# 6_Magnetorquer_Drivers.net
KiCad netlist of a schematic drawn in Altium Designer
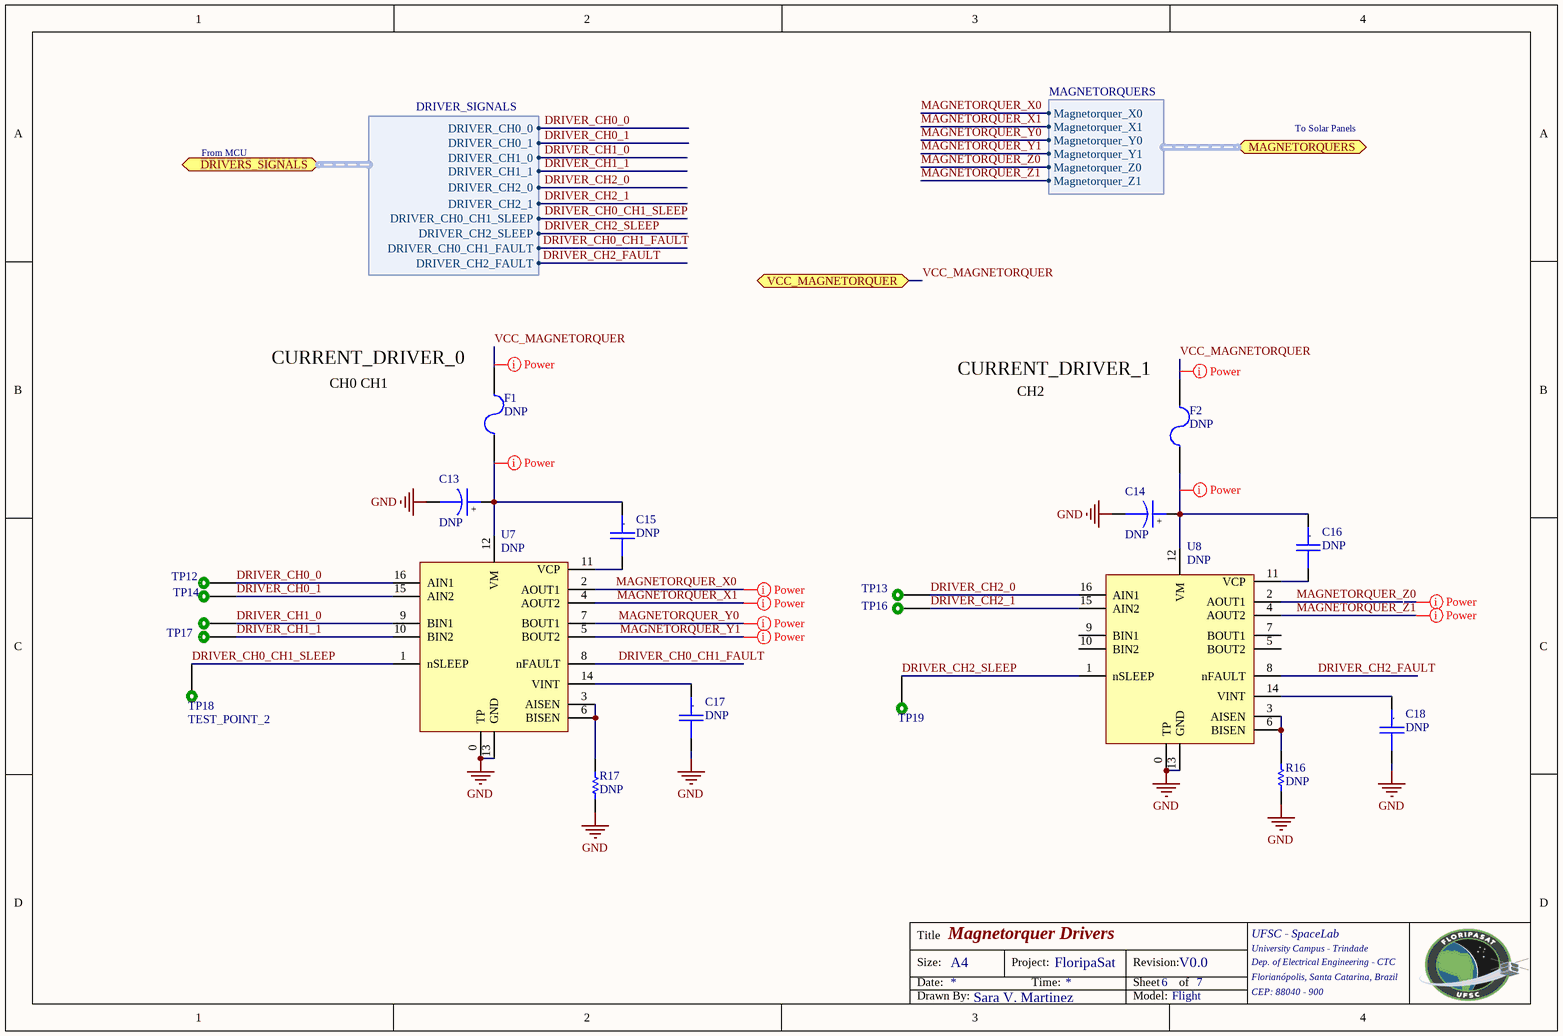
[diagram p0: 6_Magnetorquer_Drivers.SchDoc]

(export (version "E")
  (design (tool "Eeschema 10.0.6"))
  (components
    (comp (ref "C13")
      (value "DNP")
      (footprint "FloripaSatPcbLib:CC0805_Tantalum")
      (description "CAP Tantalum 10uF 10V 20% 0805")
      (fields (field (name "PARTNUMBER") "TPSP106M010R2000"))
      (libsource (lib "FloripaSatSchlib") (part "Cap_Tant_SMD_10uF_10V_0805"))
    )
    (comp (ref "C14")
      (value "DNP")
      (footprint "FloripaSatPcbLib:CC0805_Tantalum")
      (description "CAP Tantalum 10uF 10V 20% 0805")
      (fields (field (name "PARTNUMBER") "TPSP106M010R2000"))
      (libsource (lib "FloripaSatSchlib") (part "Cap_Tant_SMD_10uF_10V_0805"))
    )
    (comp (ref "C15")
      (value "DNP")
      (footprint "CC0805")
      (description "CAP CER 0.01uF 50V 10% X7R 0805")
      (fields (field (name "PARTNUMBER") "CL21B103KAANNNC"))
      (libsource (lib "FloripaSatSchlib") (part "Cap_Cer_X7R_0.01uF_50V_0805"))
    )
    (comp (ref "C16")
      (value "DNP")
      (footprint "CC0805")
      (description "CAP CER 0.01uF 50V 10% X7R 0805")
      (fields (field (name "PARTNUMBER") "CL21B103KAANNNC"))
      (libsource (lib "FloripaSatSchlib") (part "Cap_Cer_X7R_0.01uF_50V_0805"))
    )
    (comp (ref "C17")
      (value "DNP")
      (footprint "CC0805")
      (description "CAP CER 2.2uF 16V 0805")
      (fields (field (name "PARTNUMBER") "C2012X7R1C225K125AB"))
      (libsource (lib "FloripaSatSchlib") (part "Cap_Cer_X7R_2.2uF_16V_0805"))
    )
    (comp (ref "C18")
      (value "DNP")
      (footprint "CC0805")
      (description "CAP CER 2.2uF 16V 0805")
      (fields (field (name "PARTNUMBER") "C2012X7R1C225K125AB"))
      (libsource (lib "FloripaSatSchlib") (part "Cap_Cer_X7R_2.2uF_16V_0805"))
    )
    (comp (ref "F1")
      (value "DNP")
      (footprint "1206")
      (description "Surface Mount Fuses SMD FA 4A")
      (fields (field (name "PARTNUMBER") "0437.375WR") (field (name "PUBLISHER") "Altium Limited"))
      (libsource (lib "FloripaSatSchlib") (part "Fuse"))
    )
    (comp (ref "F2")
      (value "DNP")
      (footprint "1206")
      (description "Surface Mount Fuses SMD FA 4A")
      (fields (field (name "PARTNUMBER") "0437.375WR") (field (name "PUBLISHER") "Altium Limited"))
      (libsource (lib "FloripaSatSchlib") (part "Fuse"))
    )
    (comp (ref "R16")
      (value "DNP")
      (footprint "FloripaSatPcbLib:0805")
      (description "RES 0.2 OHM -0.2W 1% 0805")
      (fields (field (name "PARTNUMBER") "RL1220S-R20-F"))
      (libsource (lib "FloripaSatSchlib") (part "R0.015R_1%_0.5W_0805"))
    )
    (comp (ref "R17")
      (value "DNP")
      (footprint "FloripaSatPcbLib:0805")
      (description "RES 0.2 OHM - 0.2W 1% 0805")
      (fields (field (name "PARTNUMBER") "RL1220S-R20-F"))
      (libsource (lib "FloripaSatSchlib") (part "R0.015R_1%_0.5W_0805"))
    )
    (comp (ref "TP12")
      (value "TEST_POINT_2")
      (footprint "TEST_POINT_2")
      (description "Test point")
      (libsource (lib "FloripaSatSchlib") (part "TEST_POINT_2"))
    )
    (comp (ref "TP13")
      (value "TEST_POINT_2")
      (footprint "TEST_POINT_2")
      (description "Test point")
      (libsource (lib "FloripaSatSchlib") (part "TEST_POINT_2"))
    )
    (comp (ref "TP14")
      (value "TEST_POINT_2")
      (footprint "TEST_POINT_2")
      (description "Test point")
      (libsource (lib "FloripaSatSchlib") (part "TEST_POINT_2"))
    )
    (comp (ref "TP15")
      (value "TEST_POINT_2")
      (footprint "TEST_POINT_2")
      (description "Test point")
      (libsource (lib "FloripaSatSchlib") (part "TEST_POINT_2"))
    )
    (comp (ref "TP16")
      (value "TEST_POINT_2")
      (footprint "TEST_POINT_2")
      (description "Test point")
      (libsource (lib "FloripaSatSchlib") (part "TEST_POINT_2"))
    )
    (comp (ref "TP17")
      (value "TEST_POINT_2")
      (footprint "TEST_POINT_2")
      (description "Test point")
      (libsource (lib "FloripaSatSchlib") (part "TEST_POINT_2"))
    )
    (comp (ref "TP18")
      (value "TEST_POINT_2")
      (footprint "TEST_POINT_2")
      (description "Test point")
      (libsource (lib "FloripaSatSchlib") (part "TEST_POINT_2"))
    )
    (comp (ref "TP19")
      (value "TEST_POINT_2")
      (footprint "TEST_POINT_2")
      (description "Test point")
      (libsource (lib "FloripaSatSchlib") (part "TEST_POINT_2"))
    )
    (comp (ref "U7")
      (value "DNP")
      (footprint "16TTSSOP")
      (description "DRV8833PWPR")
      (libsource (lib "FloripaSatSchlib") (part "DRV8833PWPR"))
    )
    (comp (ref "U8")
      (value "DNP")
      (footprint "16TTSSOP")
      (description "DRV8833PWPR")
      (libsource (lib "FloripaSatSchlib") (part "DRV8833PWPR"))
    )
  )
  (nets
    (net (code "3") (name "/DRIVER_CH0_0") (class "Default")
      (node (ref "TP12") (pin "1") (pinfunction "1_1") (pintype "passive"))
      (node (ref "U7") (pin "16") (pinfunction "AIN1_16") (pintype "passive"))
    )
    (net (code "4") (name "/DRIVER_CH0_1") (class "Default")
      (node (ref "TP14") (pin "1") (pinfunction "1_1") (pintype "passive"))
      (node (ref "U7") (pin "15") (pinfunction "AIN2_15") (pintype "passive"))
    )
    (net (code "5") (name "/DRIVER_CH0_CH1_FAULT") (class "Default")
      (node (ref "U7") (pin "8") (pinfunction "nFAULT_8") (pintype "passive"))
    )
    (net (code "6") (name "/DRIVER_CH0_CH1_SLEEP") (class "Default")
      (node (ref "TP18") (pin "1") (pinfunction "1_1") (pintype "passive"))
      (node (ref "U7") (pin "1") (pinfunction "nSLEEP_1") (pintype "passive"))
    )
    (net (code "7") (name "/DRIVER_CH1_0") (class "Default")
      (node (ref "TP15") (pin "1") (pinfunction "1_1") (pintype "passive"))
      (node (ref "U7") (pin "9") (pinfunction "BIN1_9") (pintype "passive"))
    )
    (net (code "8") (name "/DRIVER_CH1_1") (class "Default")
      (node (ref "TP17") (pin "1") (pinfunction "1_1") (pintype "passive"))
      (node (ref "U7") (pin "10") (pinfunction "BIN2_10") (pintype "passive"))
    )
    (net (code "9") (name "/DRIVER_CH2_0") (class "Default")
      (node (ref "TP13") (pin "1") (pinfunction "1_1") (pintype "passive"))
      (node (ref "U8") (pin "16") (pinfunction "AIN1_16") (pintype "passive"))
    )
    (net (code "10") (name "/DRIVER_CH2_1") (class "Default")
      (node (ref "TP16") (pin "1") (pinfunction "1_1") (pintype "passive"))
      (node (ref "U8") (pin "15") (pinfunction "AIN2_15") (pintype "passive"))
    )
    (net (code "11") (name "/DRIVER_CH2_FAULT") (class "Default")
      (node (ref "U8") (pin "8") (pinfunction "nFAULT_8") (pintype "passive"))
    )
    (net (code "12") (name "/DRIVER_CH2_SLEEP") (class "Default")
      (node (ref "TP19") (pin "1") (pinfunction "1_1") (pintype "passive"))
      (node (ref "U8") (pin "1") (pinfunction "nSLEEP_1") (pintype "passive"))
    )
    (net (code "13") (name "/MAGNETORQUER_X0") (class "Default")
      (node (ref "U7") (pin "2") (pinfunction "AOUT1_2") (pintype "passive"))
    )
    (net (code "14") (name "/MAGNETORQUER_X1") (class "Default")
      (node (ref "U7") (pin "4") (pinfunction "AOUT2_4") (pintype "passive"))
    )
    (net (code "15") (name "/MAGNETORQUER_Y0") (class "Default")
      (node (ref "U7") (pin "7") (pinfunction "BOUT1_7") (pintype "passive"))
    )
    (net (code "16") (name "/MAGNETORQUER_Y1") (class "Default")
      (node (ref "U7") (pin "5") (pinfunction "BOUT2_5") (pintype "passive"))
    )
    (net (code "17") (name "/MAGNETORQUER_Z0") (class "Default")
      (node (ref "U8") (pin "2") (pinfunction "AOUT1_2") (pintype "passive"))
    )
    (net (code "18") (name "/MAGNETORQUER_Z1") (class "Default")
      (node (ref "U8") (pin "4") (pinfunction "AOUT2_4") (pintype "passive"))
    )
    (net (code "19") (name "/VCC_MAGNETORQUER") (class "Default")
      (node (ref "F1") (pin "2") (pinfunction "2_2") (pintype "passive"))
      (node (ref "F2") (pin "2") (pinfunction "2_2") (pintype "passive"))
    )
    (net (code "22") (name "GND") (class "Default")
      (node (ref "C13") (pin "2") (pinfunction "2_2") (pintype "passive"))
      (node (ref "C14") (pin "2") (pinfunction "2_2") (pintype "passive"))
      (node (ref "C17") (pin "2") (pinfunction "2_2") (pintype "passive"))
      (node (ref "C18") (pin "2") (pinfunction "2_2") (pintype "passive"))
      (node (ref "R16") (pin "1") (pinfunction "1_1") (pintype "passive"))
      (node (ref "R17") (pin "1") (pinfunction "1_1") (pintype "passive"))
      (node (ref "U7") (pin "0") (pinfunction "TP_0") (pintype "passive"))
      (node (ref "U7") (pin "13") (pinfunction "GND_13") (pintype "passive"))
      (node (ref "U8") (pin "0") (pinfunction "TP_0") (pintype "passive"))
      (node (ref "U8") (pin "13") (pinfunction "GND_13") (pintype "passive"))
    )
    (net (code "23") (name "Net-(U7-AISEN)") (class "Default")
      (node (ref "R17") (pin "2") (pinfunction "2_2") (pintype "passive"))
      (node (ref "U7") (pin "3") (pinfunction "AISEN_3") (pintype "passive"))
      (node (ref "U7") (pin "6") (pinfunction "BISEN_6") (pintype "passive"))
    )
    (net (code "24") (name "Net-(U7-VCP)") (class "Default")
      (node (ref "C15") (pin "2") (pinfunction "2_2") (pintype "passive"))
      (node (ref "U7") (pin "11") (pinfunction "VCP_11") (pintype "passive"))
    )
    (net (code "25") (name "Net-(U7-VINT)") (class "Default")
      (node (ref "C17") (pin "1") (pinfunction "1_1") (pintype "passive"))
      (node (ref "U7") (pin "14") (pinfunction "VINT_14") (pintype "passive"))
    )
    (net (code "26") (name "Net-(U7-VM)") (class "Default")
      (node (ref "C13") (pin "1") (pinfunction "1_1") (pintype "passive"))
      (node (ref "C15") (pin "1") (pinfunction "1_1") (pintype "passive"))
      (node (ref "F1") (pin "1") (pinfunction "1_1") (pintype "passive"))
      (node (ref "U7") (pin "12") (pinfunction "VM_12") (pintype "passive"))
    )
    (net (code "27") (name "Net-(U8-AISEN)") (class "Default")
      (node (ref "R16") (pin "2") (pinfunction "2_2") (pintype "passive"))
      (node (ref "U8") (pin "3") (pinfunction "AISEN_3") (pintype "passive"))
      (node (ref "U8") (pin "6") (pinfunction "BISEN_6") (pintype "passive"))
    )
    (net (code "28") (name "Net-(U8-VCP)") (class "Default")
      (node (ref "C16") (pin "2") (pinfunction "2_2") (pintype "passive"))
      (node (ref "U8") (pin "11") (pinfunction "VCP_11") (pintype "passive"))
    )
    (net (code "29") (name "Net-(U8-VINT)") (class "Default")
      (node (ref "C18") (pin "1") (pinfunction "1_1") (pintype "passive"))
      (node (ref "U8") (pin "14") (pinfunction "VINT_14") (pintype "passive"))
    )
    (net (code "30") (name "Net-(U8-VM)") (class "Default")
      (node (ref "C14") (pin "1") (pinfunction "1_1") (pintype "passive"))
      (node (ref "C16") (pin "1") (pinfunction "1_1") (pintype "passive"))
      (node (ref "F2") (pin "1") (pinfunction "1_1") (pintype "passive"))
      (node (ref "U8") (pin "12") (pinfunction "VM_12") (pintype "passive"))
    )
    (net (code "31") (name "unconnected-(U8-BIN1-Pad9)") (class "Default")
      (node (ref "U8") (pin "9") (pinfunction "BIN1_9") (pintype "passive"))
    )
    (net (code "32") (name "unconnected-(U8-BIN2-Pad10)") (class "Default")
      (node (ref "U8") (pin "10") (pinfunction "BIN2_10") (pintype "passive"))
    )
    (net (code "33") (name "unconnected-(U8-BOUT1-Pad7)") (class "Default")
      (node (ref "U8") (pin "7") (pinfunction "BOUT1_7") (pintype "passive"))
    )
    (net (code "34") (name "unconnected-(U8-BOUT2-Pad5)") (class "Default")
      (node (ref "U8") (pin "5") (pinfunction "BOUT2_5") (pintype "passive"))
    )
  )
)
